# schematic_solved.net
KiCad netlist of a schematic drawn in EAGLE
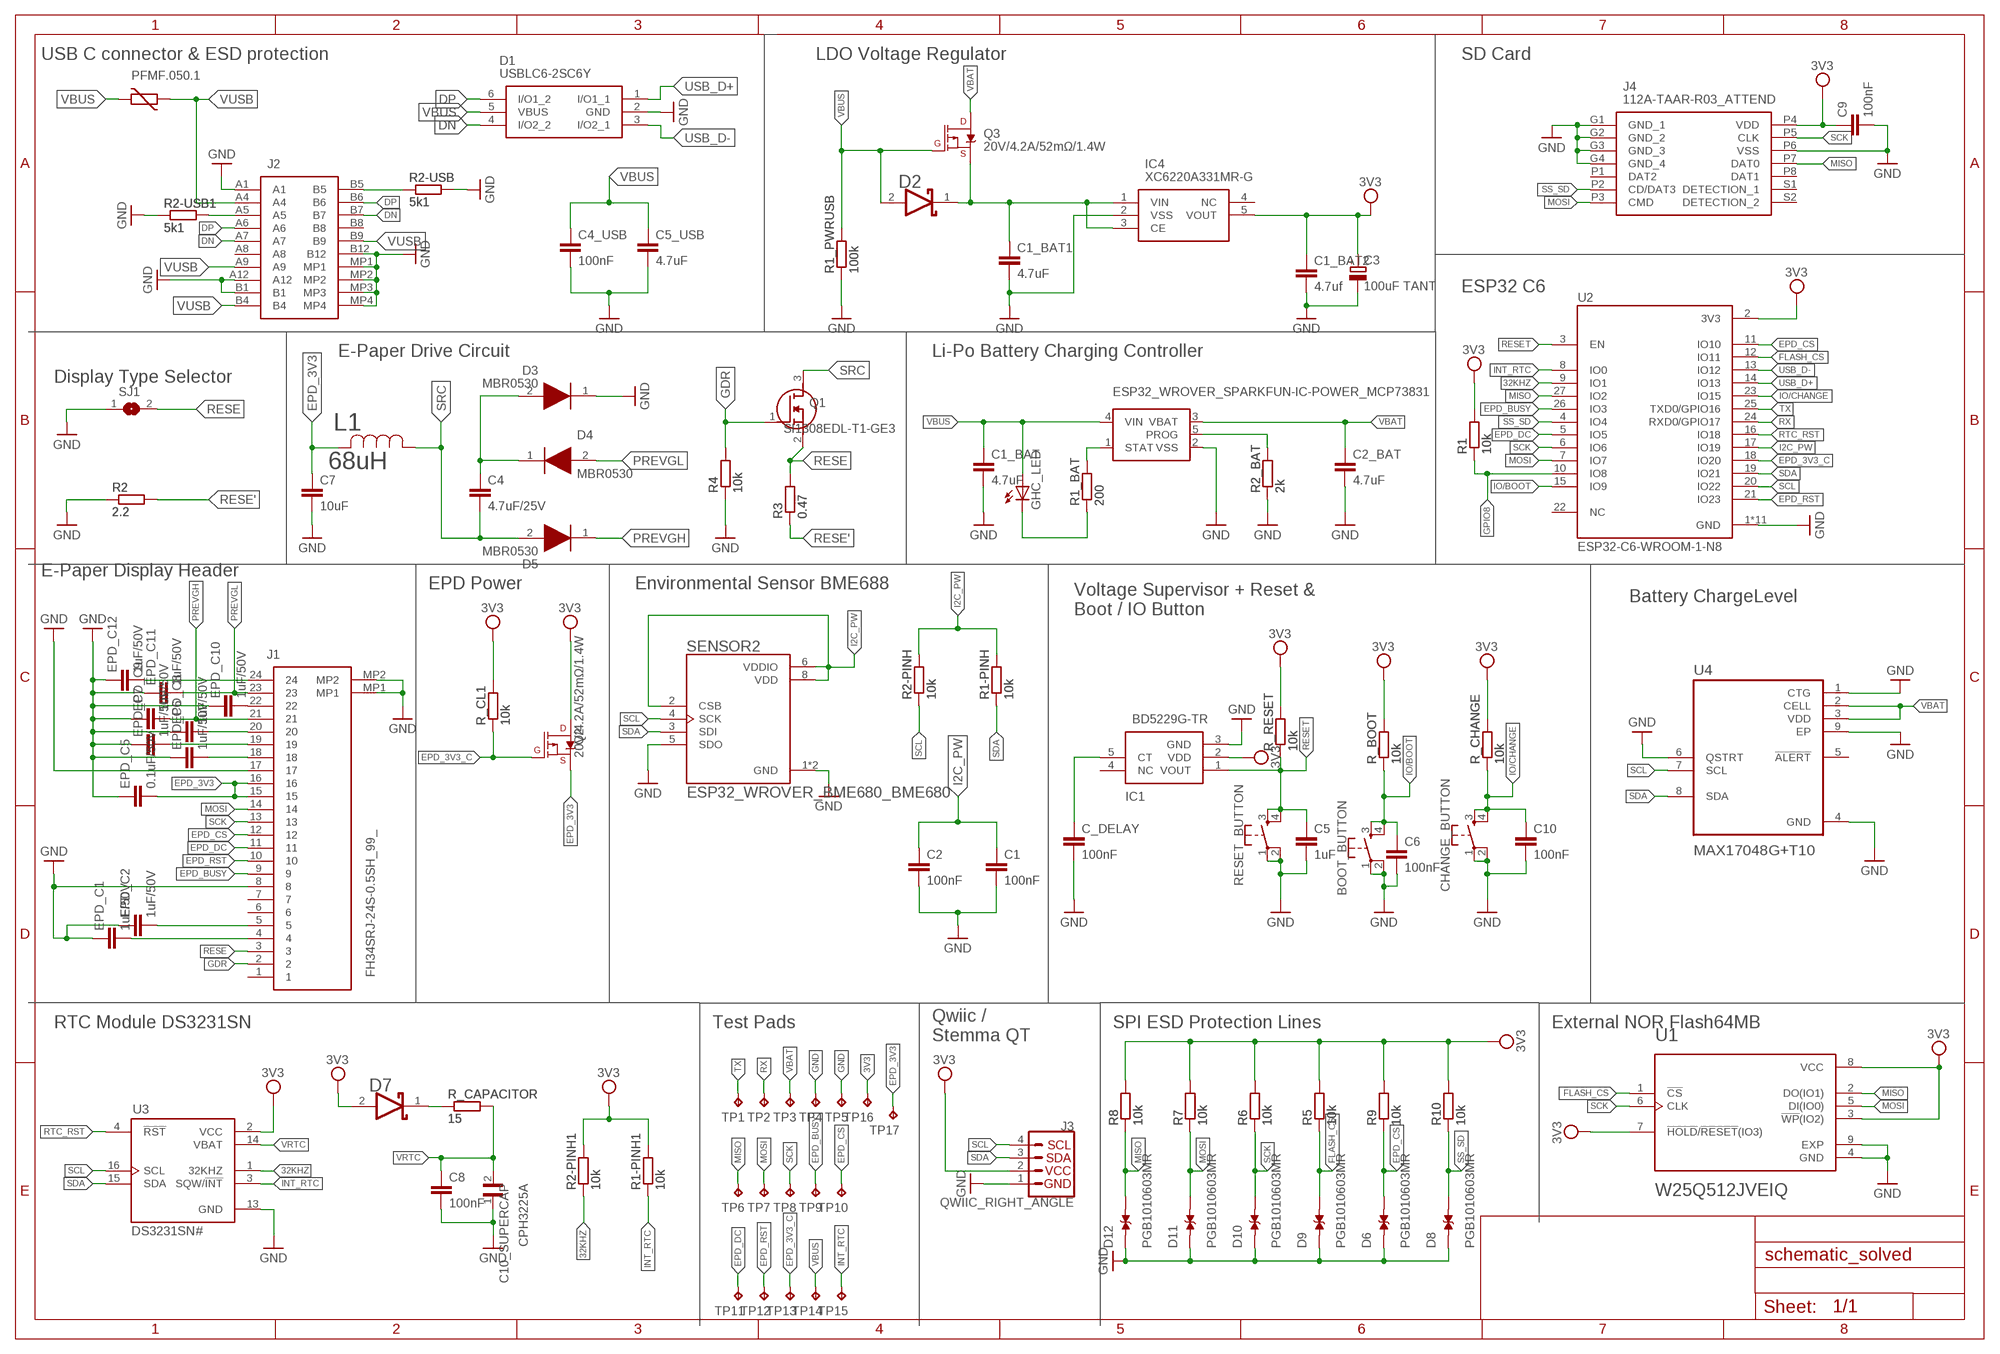
[diagram p0: schematic, sheet 1]

(export (version "E")
  (design (tool "Eeschema 10.0.6"))
  (components
    (comp (ref "BOOT_BUTTON")
      (value "BUTTON_CUSYOMV1")
      (footprint "eagle-import:MYBUTTON")
      (libsource (lib "eagle-import") (part "BUTTON_CUSYOMV1"))
    )
    (comp (ref "C1")
      (value "100nF")
      (footprint "eagle-import:ESP32_WROVER_EAGLE-LTSPICE_C0402")
      (libsource (lib "eagle-import") (part "ESP32_WROVER_EAGLE-LTSPICE_CC0402"))
    )
    (comp (ref "C1_BAT")
      (value "4.7uF")
      (footprint "eagle-import:EAGLE-LTSPICE_C0402")
      (libsource (lib "eagle-import") (part "EAGLE-LTSPICE_CC0402"))
    )
    (comp (ref "C1_BAT1")
      (value "4.7uF")
      (footprint "eagle-import:EAGLE-LTSPICE_C0402")
      (libsource (lib "eagle-import") (part "EAGLE-LTSPICE_CC0402"))
    )
    (comp (ref "C1_BAT2")
      (value "4.7uf")
      (footprint "eagle-import:EAGLE-LTSPICE_C0402")
      (libsource (lib "eagle-import") (part "EAGLE-LTSPICE_CC0402"))
    )
    (comp (ref "C2")
      (value "100nF")
      (footprint "eagle-import:ESP32_WROVER_EAGLE-LTSPICE_C0402")
      (libsource (lib "eagle-import") (part "ESP32_WROVER_EAGLE-LTSPICE_CC0402"))
    )
    (comp (ref "C2_BAT")
      (value "4.7uF")
      (footprint "eagle-import:EAGLE-LTSPICE_C0402")
      (libsource (lib "eagle-import") (part "EAGLE-LTSPICE_CC0402"))
    )
    (comp (ref "C3")
      (value "100uF TANT")
      (footprint "eagle-import:RCL_CT3528")
      (libsource (lib "eagle-import") (part "RCL_CPOL-EUCT3528"))
    )
    (comp (ref "C4")
      (value "4.7uF/25V")
      (footprint "eagle-import:ESP32_WROVER_EAGLE-LTSPICE_C0402")
      (libsource (lib "eagle-import") (part "ESP32_WROVER_EAGLE-LTSPICE_CC0402"))
    )
    (comp (ref "C4_USB")
      (value "100nF")
      (footprint "eagle-import:ESP32_WROVER_EAGLE-LTSPICE_C0402")
      (libsource (lib "eagle-import") (part "ESP32_WROVER_EAGLE-LTSPICE_CC0402"))
    )
    (comp (ref "C5")
      (value "1uF")
      (footprint "eagle-import:ESP32_WROVER_EAGLE-LTSPICE_C0402")
      (libsource (lib "eagle-import") (part "ESP32_WROVER_EAGLE-LTSPICE_CC0402"))
    )
    (comp (ref "C5_USB")
      (value "4.7uF")
      (footprint "eagle-import:ESP32_WROVER_EAGLE-LTSPICE_C0402")
      (libsource (lib "eagle-import") (part "ESP32_WROVER_EAGLE-LTSPICE_CC0402"))
    )
    (comp (ref "C6")
      (value "100nF")
      (footprint "eagle-import:ESP32_WROVER_EAGLE-LTSPICE_C0402")
      (libsource (lib "eagle-import") (part "ESP32_WROVER_EAGLE-LTSPICE_CC0402"))
    )
    (comp (ref "C7")
      (value "10uF")
      (footprint "eagle-import:ESP32_WROVER_EAGLE-LTSPICE_C0402")
      (libsource (lib "eagle-import") (part "ESP32_WROVER_EAGLE-LTSPICE_CC0402"))
    )
    (comp (ref "C8")
      (value "100nF")
      (footprint "eagle-import:ESP32_WROVER_EAGLE-LTSPICE_C0402")
      (libsource (lib "eagle-import") (part "ESP32_WROVER_EAGLE-LTSPICE_CC0402"))
    )
    (comp (ref "C9")
      (value "100nF")
      (footprint "eagle-import:ESP32_WROVER_EAGLE-LTSPICE_C0402")
      (libsource (lib "eagle-import") (part "ESP32_WROVER_EAGLE-LTSPICE_CC0402"))
    )
    (comp (ref "C10")
      (value "100nF")
      (footprint "eagle-import:ESP32_WROVER_EAGLE-LTSPICE_C0402")
      (libsource (lib "eagle-import") (part "ESP32_WROVER_EAGLE-LTSPICE_CC0402"))
    )
    (comp (ref "C10_SUPERCAP")
      (value "CPH3225A")
      (footprint "eagle-import:CAPCP3225X100N")
      (fields (field (name "MF") "Seiko Instruments"))
      (libsource (lib "eagle-import") (part "CPH3225A"))
    )
    (comp (ref "CHANGE_BUTTON")
      (value "BUTTON_CUSYOMV1")
      (footprint "eagle-import:MYBUTTON")
      (libsource (lib "eagle-import") (part "BUTTON_CUSYOMV1"))
    )
    (comp (ref "C_DELAY")
      (value "100nF")
      (footprint "eagle-import:ESP32_WROVER_EAGLE-LTSPICE_C0402")
      (libsource (lib "eagle-import") (part "ESP32_WROVER_EAGLE-LTSPICE_CC0402"))
    )
    (comp (ref "D1")
      (value "USBLC6-2SC6Y")
      (footprint "eagle-import:SOT95P280X145-6N")
      (fields (field (name "MF") "STMicroelectronics"))
      (libsource (lib "eagle-import") (part "USBLC6-2SC6Y"))
    )
    (comp (ref "D2")
      (value "ESP32_WROVER_AVX---SD0805S020S1R0_AVX_SD0805S020S1R0_0_0AVX_SD0805S020S1R0_0_0")
      (footprint "eagle-import:ESP32_WROVER_AVX---SD0805S020S1R0_AVX_SD0805S020S1R0_0")
      (fields
        (field (name "DIGIKEY_PART_NUMBER") "478-7800-1-ND")
        (field (name "MF") "AVX")
        (field (name "MOUSER_PART_NUMBER") "581-SD0805S020S1R0")
      )
      (libsource (lib "eagle-import") (part "ESP32_WROVER_AVX---SD0805S020S1R0_AVX_SD0805S020S1R0_0_0AVX_SD0805S020S1R0_0_0"))
    )
    (comp (ref "D3")
      (value "MBR0530")
      (footprint "eagle-import:SOD3716X135N")
      (fields (field (name "MF") "ON Semiconductor"))
      (libsource (lib "eagle-import") (part "MBR0530"))
    )
    (comp (ref "D4")
      (value "MBR0530")
      (footprint "eagle-import:SOD3716X135N")
      (fields (field (name "MF") "ON Semiconductor"))
      (libsource (lib "eagle-import") (part "MBR0530"))
    )
    (comp (ref "D5")
      (value "MBR0530")
      (footprint "eagle-import:SOD3716X135N")
      (fields (field (name "MF") "ON Semiconductor"))
      (libsource (lib "eagle-import") (part "MBR0530"))
    )
    (comp (ref "D6")
      (value "PGB1010603MR")
      (footprint "eagle-import:DIOC1608X36N")
      (fields (field (name "MF") "Littelfuse Inc."))
      (libsource (lib "eagle-import") (part "PGB1010603MR"))
    )
    (comp (ref "D7")
      (value "ESP32_WROVER_AVX---SD0805S020S1R0_AVX_SD0805S020S1R0_0_0AVX_SD0805S020S1R0_0_0")
      (footprint "eagle-import:ESP32_WROVER_AVX---SD0805S020S1R0_AVX_SD0805S020S1R0_0")
      (fields
        (field (name "DIGIKEY_PART_NUMBER") "478-7800-1-ND")
        (field (name "MF") "AVX")
        (field (name "MOUSER_PART_NUMBER") "581-SD0805S020S1R0")
      )
      (libsource (lib "eagle-import") (part "ESP32_WROVER_AVX---SD0805S020S1R0_AVX_SD0805S020S1R0_0_0AVX_SD0805S020S1R0_0_0"))
    )
    (comp (ref "D8")
      (value "PGB1010603MR")
      (footprint "eagle-import:DIOC1608X36N")
      (fields (field (name "MF") "Littelfuse Inc."))
      (libsource (lib "eagle-import") (part "PGB1010603MR"))
    )
    (comp (ref "D9")
      (value "PGB1010603MR")
      (footprint "eagle-import:DIOC1608X36N")
      (fields (field (name "MF") "Littelfuse Inc."))
      (libsource (lib "eagle-import") (part "PGB1010603MR"))
    )
    (comp (ref "D10")
      (value "PGB1010603MR")
      (footprint "eagle-import:DIOC1608X36N")
      (fields (field (name "MF") "Littelfuse Inc."))
      (libsource (lib "eagle-import") (part "PGB1010603MR"))
    )
    (comp (ref "D11")
      (value "PGB1010603MR")
      (footprint "eagle-import:DIOC1608X36N")
      (fields (field (name "MF") "Littelfuse Inc."))
      (libsource (lib "eagle-import") (part "PGB1010603MR"))
    )
    (comp (ref "D12")
      (value "PGB1010603MR")
      (footprint "eagle-import:DIOC1608X36N")
      (fields (field (name "MF") "Littelfuse Inc."))
      (libsource (lib "eagle-import") (part "PGB1010603MR"))
    )
    (comp (ref "EPD_C1")
      (value "1uF/50V")
      (footprint "eagle-import:ESP32_WROVER_EAGLE-LTSPICE_C0402")
      (libsource (lib "eagle-import") (part "ESP32_WROVER_EAGLE-LTSPICE_CC0402"))
    )
    (comp (ref "EPD_C2")
      (value "1uF/50V")
      (footprint "eagle-import:ESP32_WROVER_EAGLE-LTSPICE_C0402")
      (libsource (lib "eagle-import") (part "ESP32_WROVER_EAGLE-LTSPICE_CC0402"))
    )
    (comp (ref "EPD_C5")
      (value "0.1uF/50V")
      (footprint "eagle-import:ESP32_WROVER_EAGLE-LTSPICE_C0402")
      (libsource (lib "eagle-import") (part "ESP32_WROVER_EAGLE-LTSPICE_CC0402"))
    )
    (comp (ref "EPD_C6")
      (value "1uF/50V")
      (footprint "eagle-import:ESP32_WROVER_EAGLE-LTSPICE_C0402")
      (libsource (lib "eagle-import") (part "ESP32_WROVER_EAGLE-LTSPICE_CC0402"))
    )
    (comp (ref "EPD_C7")
      (value "1uF/50V")
      (footprint "eagle-import:ESP32_WROVER_EAGLE-LTSPICE_C0402")
      (libsource (lib "eagle-import") (part "ESP32_WROVER_EAGLE-LTSPICE_CC0402"))
    )
    (comp (ref "EPD_C8")
      (value "1uF/50V")
      (footprint "eagle-import:ESP32_WROVER_EAGLE-LTSPICE_C0402")
      (libsource (lib "eagle-import") (part "ESP32_WROVER_EAGLE-LTSPICE_CC0402"))
    )
    (comp (ref "EPD_C9")
      (value "1uF/50V")
      (footprint "eagle-import:ESP32_WROVER_EAGLE-LTSPICE_C0402")
      (libsource (lib "eagle-import") (part "ESP32_WROVER_EAGLE-LTSPICE_CC0402"))
    )
    (comp (ref "EPD_C10")
      (value "1uF/50V")
      (footprint "eagle-import:ESP32_WROVER_EAGLE-LTSPICE_C0402")
      (libsource (lib "eagle-import") (part "ESP32_WROVER_EAGLE-LTSPICE_CC0402"))
    )
    (comp (ref "EPD_C11")
      (value "1uF/50V")
      (footprint "eagle-import:ESP32_WROVER_EAGLE-LTSPICE_C0402")
      (libsource (lib "eagle-import") (part "ESP32_WROVER_EAGLE-LTSPICE_CC0402"))
    )
    (comp (ref "EPD_C12")
      (value "1uF/50V")
      (footprint "eagle-import:ESP32_WROVER_EAGLE-LTSPICE_C0402")
      (libsource (lib "eagle-import") (part "ESP32_WROVER_EAGLE-LTSPICE_CC0402"))
    )
    (comp (ref "GHC_LED")
      (value "ADAFRUIT_LEDCHIP-LED0603")
      (footprint "eagle-import:ADAFRUIT_CHIP-LED0603")
      (libsource (lib "eagle-import") (part "ADAFRUIT_LEDCHIP-LED0603"))
    )
    (comp (ref "IC1")
      (value "BD5229G-TR")
      (footprint "eagle-import:SOT95P280X125-5N")
      (fields (field (name "MOUSER_PART_NUMBER") "755-BD5229G-TR"))
      (libsource (lib "eagle-import") (part "BD5229G-TR"))
    )
    (comp (ref "IC4")
      (value "XC6220A331MR-G")
      (footprint "eagle-import:SOT95P280X120-5N")
      (fields (field (name "MOUSER_PART_NUMBER") "865-XC6220A331MR-G"))
      (libsource (lib "eagle-import") (part "XC6220A331MR-G"))
    )
    (comp (ref "J1")
      (value "FH34SRJ-24S-0.5SH_99_")
      (footprint "eagle-import:FH34SRJ24S05SH99")
      (fields
        (field (name "MANUFACTURER_PART_NUMBER") "FH34SRJ-24S-0.5SH(99)")
        (field (name "MOUSER_PART_NUMBER") "798-FH34SRJ24S05SH99")
      )
      (libsource (lib "eagle-import") (part "FH34SRJ-24S-0.5SH_99_"))
    )
    (comp (ref "J2")
      (value "SAMACSYS_PARTS_USB4110-GF-A")
      (footprint "eagle-import:SAMACSYS_PARTS_USB4110GFA")
      (fields
        (field (name "MANUFACTURER_PART_NUMBER") "USB4110-GF-A")
        (field (name "MOUSER_PART_NUMBER") "640-USB4110-GF-A")
      )
      (libsource (lib "eagle-import") (part "SAMACSYS_PARTS_USB4110-GF-A"))
    )
    (comp (ref "J3")
      (value "QWIIC_RIGHT_ANGLE")
      (footprint "eagle-import:JST04_1MM_RA")
      (libsource (lib "eagle-import") (part "QWIIC_CONNECTORJS-1MM"))
    )
    (comp (ref "J4")
      (value "112A-TAAR-R03_ATTEND")
      (footprint "eagle-import:112ATAARR03ATTEND")
      (fields (field (name "MANUFACTURER_PART_NUMBER") "112A-TAAR-R03 ATTEND"))
      (libsource (lib "eagle-import") (part "112A-TAAR-R03_ATTEND"))
    )
    (comp (ref "L1")
      (value "68uH")
      (footprint "eagle-import:IND_4828-WE-TPC_WRE")
      (fields
        (field (name "MANUFACTURER_PART_NUMBER") "744043680")
        (field (name "COPYRIGHT") "Copyright (C) 2024 Ultra Librarian. All rights reserved.")
      )
      (libsource (lib "eagle-import") (part "744043680IND_4828-WE-TPC_WRE"))
    )
    (comp (ref "PFMF.050.1")
      (value "ESP32C6_VARISTORCN1812")
      (footprint "eagle-import:ESP32C6_VARISTOR_CT_CN1812")
      (libsource (lib "eagle-import") (part "ESP32C6_VARISTORCN1812"))
    )
    (comp (ref "Q1")
      (value "SI1308EDL-T1-GE3")
      (footprint "eagle-import:SOT65P210X110-3N")
      (fields (field (name "MF") "Vishay Siliconix"))
      (libsource (lib "eagle-import") (part "SI1308EDL-T1-GE3"))
    )
    (comp (ref "Q2")
      (value "20V/4.2A/52mΩ/1.4W")
      (footprint "eagle-import:ESP32_WROVER_SPARKFUN-DISCRETESEMI_SOT23-3")
      (libsource (lib "eagle-import") (part "ESP32_WROVER_SPARKFUN-DISCRETESEMI_MOSFET_PCH-DMG2305UX-7"))
    )
    (comp (ref "Q3")
      (value "20V/4.2A/52mΩ/1.4W")
      (footprint "eagle-import:ESP32_WROVER_SPARKFUN-DISCRETESEMI_SOT23-3")
      (libsource (lib "eagle-import") (part "ESP32_WROVER_SPARKFUN-DISCRETESEMI_MOSFET_PCH-DMG2305UX-7"))
    )
    (comp (ref "R1")
      (value "10k")
      (footprint "eagle-import:ESP32_WROVER_EAGLE-LTSPICE_R0402")
      (libsource (lib "eagle-import") (part "ESP32_WROVER_EAGLE-LTSPICE_RR0402"))
    )
    (comp (ref "R1-PINH")
      (value "10k")
      (footprint "eagle-import:ESP32_WROVER_EAGLE-LTSPICE_R0402")
      (libsource (lib "eagle-import") (part "ESP32_WROVER_EAGLE-LTSPICE_RR0402"))
    )
    (comp (ref "R1-PINH1")
      (value "10k")
      (footprint "eagle-import:ESP32_WROVER_EAGLE-LTSPICE_R0402")
      (libsource (lib "eagle-import") (part "ESP32_WROVER_EAGLE-LTSPICE_RR0402"))
    )
    (comp (ref "R1_BAT")
      (value "200")
      (footprint "eagle-import:ESP32_WROVER_EAGLE-LTSPICE_R0402")
      (libsource (lib "eagle-import") (part "ESP32_WROVER_EAGLE-LTSPICE_RR0402"))
    )
    (comp (ref "R1_PWRUSB")
      (value "100k")
      (footprint "eagle-import:ESP32_WROVER_EAGLE-LTSPICE_R0402")
      (libsource (lib "eagle-import") (part "ESP32_WROVER_EAGLE-LTSPICE_RR0402"))
    )
    (comp (ref "R2")
      (value "2.2")
      (footprint "eagle-import:ESP32_WROVER_EAGLE-LTSPICE_R0402")
      (libsource (lib "eagle-import") (part "ESP32_WROVER_EAGLE-LTSPICE_RR0402"))
    )
    (comp (ref "R2-PINH")
      (value "10k")
      (footprint "eagle-import:ESP32_WROVER_EAGLE-LTSPICE_R0402")
      (libsource (lib "eagle-import") (part "ESP32_WROVER_EAGLE-LTSPICE_RR0402"))
    )
    (comp (ref "R2-PINH1")
      (value "10k")
      (footprint "eagle-import:ESP32_WROVER_EAGLE-LTSPICE_R0402")
      (libsource (lib "eagle-import") (part "ESP32_WROVER_EAGLE-LTSPICE_RR0402"))
    )
    (comp (ref "R2-USB")
      (value "5k1")
      (footprint "eagle-import:ESP32_WROVER_EAGLE-LTSPICE_R0402")
      (libsource (lib "eagle-import") (part "ESP32_WROVER_EAGLE-LTSPICE_RR0402"))
    )
    (comp (ref "R2-USB1")
      (value "5k1")
      (footprint "eagle-import:ESP32_WROVER_EAGLE-LTSPICE_R0402")
      (libsource (lib "eagle-import") (part "ESP32_WROVER_EAGLE-LTSPICE_RR0402"))
    )
    (comp (ref "R2_BAT")
      (value "2k")
      (footprint "eagle-import:ESP32_WROVER_EAGLE-LTSPICE_R0402")
      (libsource (lib "eagle-import") (part "ESP32_WROVER_EAGLE-LTSPICE_RR0402"))
    )
    (comp (ref "R3")
      (value "0.47")
      (footprint "eagle-import:ESP32_WROVER_EAGLE-LTSPICE_R0402")
      (libsource (lib "eagle-import") (part "ESP32_WROVER_EAGLE-LTSPICE_RR0402"))
    )
    (comp (ref "R4")
      (value "10k")
      (footprint "eagle-import:ESP32_WROVER_EAGLE-LTSPICE_R0402")
      (libsource (lib "eagle-import") (part "ESP32_WROVER_EAGLE-LTSPICE_RR0402"))
    )
    (comp (ref "R5")
      (value "10k")
      (footprint "eagle-import:ESP32_WROVER_EAGLE-LTSPICE_R0402")
      (libsource (lib "eagle-import") (part "ESP32_WROVER_EAGLE-LTSPICE_RR0402"))
    )
    (comp (ref "R6")
      (value "10k")
      (footprint "eagle-import:ESP32_WROVER_EAGLE-LTSPICE_R0402")
      (libsource (lib "eagle-import") (part "ESP32_WROVER_EAGLE-LTSPICE_RR0402"))
    )
    (comp (ref "R7")
      (value "10k")
      (footprint "eagle-import:ESP32_WROVER_EAGLE-LTSPICE_R0402")
      (libsource (lib "eagle-import") (part "ESP32_WROVER_EAGLE-LTSPICE_RR0402"))
    )
    (comp (ref "R8")
      (value "10k")
      (footprint "eagle-import:ESP32_WROVER_EAGLE-LTSPICE_R0402")
      (libsource (lib "eagle-import") (part "ESP32_WROVER_EAGLE-LTSPICE_RR0402"))
    )
    (comp (ref "R9")
      (value "10k")
      (footprint "eagle-import:ESP32_WROVER_EAGLE-LTSPICE_R0402")
      (libsource (lib "eagle-import") (part "ESP32_WROVER_EAGLE-LTSPICE_RR0402"))
    )
    (comp (ref "R10")
      (value "10k")
      (footprint "eagle-import:ESP32_WROVER_EAGLE-LTSPICE_R0402")
      (libsource (lib "eagle-import") (part "ESP32_WROVER_EAGLE-LTSPICE_RR0402"))
    )
    (comp (ref "RESET_BUTTON")
      (value "BUTTON_CUSYOMV1")
      (footprint "eagle-import:MYBUTTON")
      (libsource (lib "eagle-import") (part "BUTTON_CUSYOMV1"))
    )
    (comp (ref "R_BOOT")
      (value "10k")
      (footprint "eagle-import:ESP32_WROVER_EAGLE-LTSPICE_R0402")
      (libsource (lib "eagle-import") (part "ESP32_WROVER_EAGLE-LTSPICE_RR0402"))
    )
    (comp (ref "R_CAPACITOR")
      (value "15")
      (footprint "eagle-import:ESP32_WROVER_EAGLE-LTSPICE_R0402")
      (libsource (lib "eagle-import") (part "ESP32_WROVER_EAGLE-LTSPICE_RR0402"))
    )
    (comp (ref "R_CHANGE")
      (value "10k")
      (footprint "eagle-import:ESP32_WROVER_EAGLE-LTSPICE_R0402")
      (libsource (lib "eagle-import") (part "ESP32_WROVER_EAGLE-LTSPICE_RR0402"))
    )
    (comp (ref "R_CL1")
      (value "10k")
      (footprint "eagle-import:ESP32_WROVER_EAGLE-LTSPICE_R0402")
      (libsource (lib "eagle-import") (part "ESP32_WROVER_EAGLE-LTSPICE_RR0402"))
    )
    (comp (ref "R_RESET")
      (value "10k")
      (footprint "eagle-import:ESP32_WROVER_EAGLE-LTSPICE_R0402")
      (libsource (lib "eagle-import") (part "ESP32_WROVER_EAGLE-LTSPICE_RR0402"))
    )
    (comp (ref "SENSOR2")
      (value "ESP32_WROVER_BME680_BME680")
      (footprint "eagle-import:ESP32_WROVER_BME680_PSON80P300X300X100-8N")
      (fields (field (name "MF") "Bosch Sensortec") (field (name "MP") "BME680"))
      (libsource (lib "eagle-import") (part "ESP32_WROVER_BME680_BME680"))
    )
    (comp (ref "SJ1") (value "SJ") (footprint "eagle-import:SJ") (libsource (lib "eagle-import") (part "SJ")))
    (comp (ref "TP1")
      (value "TPTP20R")
      (footprint "eagle-import:TP20R")
      (libsource (lib "eagle-import") (part "TPTP20R"))
    )
    (comp (ref "TP2")
      (value "TPTP20R")
      (footprint "eagle-import:TP20R")
      (libsource (lib "eagle-import") (part "TPTP20R"))
    )
    (comp (ref "TP3")
      (value "TPTP20R")
      (footprint "eagle-import:TP20R")
      (libsource (lib "eagle-import") (part "TPTP20R"))
    )
    (comp (ref "TP4")
      (value "TPTP20R")
      (footprint "eagle-import:TP20R")
      (libsource (lib "eagle-import") (part "TPTP20R"))
    )
    (comp (ref "TP5")
      (value "TPTP20R")
      (footprint "eagle-import:TP20R")
      (libsource (lib "eagle-import") (part "TPTP20R"))
    )
    (comp (ref "TP6")
      (value "TPTP20R")
      (footprint "eagle-import:TP20R")
      (libsource (lib "eagle-import") (part "TPTP20R"))
    )
    (comp (ref "TP7")
      (value "TPTP20R")
      (footprint "eagle-import:TP20R")
      (libsource (lib "eagle-import") (part "TPTP20R"))
    )
    (comp (ref "TP8")
      (value "TPTP20R")
      (footprint "eagle-import:TP20R")
      (libsource (lib "eagle-import") (part "TPTP20R"))
    )
    (comp (ref "TP9")
      (value "TPTP20R")
      (footprint "eagle-import:TP20R")
      (libsource (lib "eagle-import") (part "TPTP20R"))
    )
    (comp (ref "TP10")
      (value "TPTP20R")
      (footprint "eagle-import:TP20R")
      (libsource (lib "eagle-import") (part "TPTP20R"))
    )
    (comp (ref "TP11")
      (value "TPTP20R")
      (footprint "eagle-import:TP20R")
      (libsource (lib "eagle-import") (part "TPTP20R"))
    )
    (comp (ref "TP12")
      (value "TPTP20R")
      (footprint "eagle-import:TP20R")
      (libsource (lib "eagle-import") (part "TPTP20R"))
    )
    (comp (ref "TP13")
      (value "TPTP20R")
      (footprint "eagle-import:TP20R")
      (libsource (lib "eagle-import") (part "TPTP20R"))
    )
    (comp (ref "TP14")
      (value "TPTP20R")
      (footprint "eagle-import:TP20R")
      (libsource (lib "eagle-import") (part "TPTP20R"))
    )
    (comp (ref "TP15")
      (value "TPTP20R")
      (footprint "eagle-import:TP20R")
      (libsource (lib "eagle-import") (part "TPTP20R"))
    )
    (comp (ref "TP16")
      (value "TPTP20R")
      (footprint "eagle-import:TP20R")
      (libsource (lib "eagle-import") (part "TPTP20R"))
    )
    (comp (ref "TP17")
      (value "TPTP20R")
      (footprint "eagle-import:TP20R")
      (libsource (lib "eagle-import") (part "TPTP20R"))
    )
    (comp (ref "U")
      (value "ESP32_WROVER_SPARKFUN-IC-POWER_MCP73831")
      (footprint "eagle-import:ESP32_WROVER_SPARKFUN-IC-POWER_SOT23-5")
      (libsource (lib "eagle-import") (part "ESP32_WROVER_SPARKFUN-IC-POWER_MCP73831"))
    )
    (comp (ref "U1")
      (value "W25Q512JVEIQ")
      (footprint "eagle-import:SON127P600X800X80-9N")
      (fields (field (name "MF") "Winbond Electronics"))
      (libsource (lib "eagle-import") (part "W25Q512JVEIQ"))
    )
    (comp (ref "U2")
      (value "ESP32-C6-WROOM-1-N8")
      (footprint "eagle-import:XCVR_ESP32-C6-WROOM-1-N8")
      (fields (field (name "MF") "Espressif Systems"))
      (libsource (lib "eagle-import") (part "ESP32-C6-WROOM-1-N8"))
    )
    (comp (ref "U3")
      (value "DS3231SN#")
      (footprint "eagle-import:SOIC127P1032X265-16N")
      (fields (field (name "MF") "Analog Devices"))
      (libsource (lib "eagle-import") (part "DS3231SN#"))
    )
    (comp (ref "U4")
      (value "MAX17048G+T10")
      (footprint "eagle-import:SON50P200X200X80-9N")
      (fields (field (name "MF") "Analog Devices"))
      (libsource (lib "eagle-import") (part "MAX17048G+T10"))
    )
  )
  (nets
    (net (code "1") (name "3V3") (class "Default")
      (node (ref "C1_BAT2") (pin "1") (pinfunction "1_1") (pintype "passive"))
      (node (ref "C3") (pin "+") (pinfunction "+_+") (pintype "passive"))
      (node (ref "C9") (pin "1") (pinfunction "1_1") (pintype "passive"))
      (node (ref "D7") (pin "2") (pinfunction "ANODE_2") (pintype "bidirectional"))
      (node (ref "IC1") (pin "2") (pinfunction "VDD_2") (pintype "bidirectional"))
      (node (ref "IC4") (pin "5") (pinfunction "VOUT_5") (pintype "bidirectional"))
      (node (ref "J3") (pin "2") (pinfunction "2_2") (pintype "power_in"))
      (node (ref "J4") (pin "P4") (pinfunction "VDD_P4") (pintype "bidirectional"))
      (node (ref "Q2") (pin "3") (pinfunction "D_3") (pintype "bidirectional"))
      (node (ref "R1") (pin "2") (pinfunction "2_2") (pintype "passive"))
      (node (ref "R1-PINH1") (pin "2") (pinfunction "2_2") (pintype "passive"))
      (node (ref "R10") (pin "2") (pinfunction "2_2") (pintype "passive"))
      (node (ref "R2-PINH1") (pin "2") (pinfunction "2_2") (pintype "passive"))
      (node (ref "R5") (pin "2") (pinfunction "2_2") (pintype "passive"))
      (node (ref "R6") (pin "2") (pinfunction "2_2") (pintype "passive"))
      (node (ref "R7") (pin "2") (pinfunction "2_2") (pintype "passive"))
      (node (ref "R8") (pin "2") (pinfunction "2_2") (pintype "passive"))
      (node (ref "R9") (pin "2") (pinfunction "2_2") (pintype "passive"))
      (node (ref "R_BOOT") (pin "2") (pinfunction "2_2") (pintype "passive"))
      (node (ref "R_CHANGE") (pin "2") (pinfunction "2_2") (pintype "passive"))
      (node (ref "R_CL1") (pin "2") (pinfunction "2_2") (pintype "passive"))
      (node (ref "R_RESET") (pin "2") (pinfunction "2_2") (pintype "passive"))
      (node (ref "TP16") (pin "TP") (pinfunction "TP_TP") (pintype "input"))
      (node (ref "U1") (pin "3") (pinfunction "~{WP}(IO2)_3") (pintype "bidirectional"))
      (node (ref "U1") (pin "7") (pinfunction "~{HOLD}/~{RESET}(IO3)_7") (pintype "bidirectional"))
      (node (ref "U1") (pin "8") (pinfunction "VCC_8") (pintype "power_in"))
      (node (ref "U2") (pin "2") (pinfunction "3V3_2") (pintype "power_in"))
      (node (ref "U3") (pin "2") (pinfunction "VCC_2") (pintype "power_in"))
    )
    (net (code "2") (name "32KHZ") (class "Default")
      (node (ref "R2-PINH1") (pin "1") (pinfunction "1_1") (pintype "passive"))
      (node (ref "U2") (pin "9") (pinfunction "IO1_9") (pintype "bidirectional"))
      (node (ref "U3") (pin "1") (pinfunction "32KHZ_1") (pintype "output"))
    )
    (net (code "3") (name "DN") (class "Default")
      (node (ref "D1") (pin "4") (pinfunction "I/O2_2_4") (pintype "bidirectional"))
      (node (ref "J2") (pin "A7") (pinfunction "A7_A7") (pintype "bidirectional"))
      (node (ref "J2") (pin "B7") (pinfunction "B7_B7") (pintype "bidirectional"))
    )
    (net (code "4") (name "DP") (class "Default")
      (node (ref "D1") (pin "6") (pinfunction "I/O1_2_6") (pintype "bidirectional"))
      (node (ref "J2") (pin "A6") (pinfunction "A6_A6") (pintype "bidirectional"))
      (node (ref "J2") (pin "B6") (pinfunction "B6_B6") (pintype "bidirectional"))
    )
    (net (code "5") (name "EPD_3V3") (class "Default")
      (node (ref "C7") (pin "1") (pinfunction "1_1") (pintype "passive"))
      (node (ref "EPD_C5") (pin "2") (pinfunction "2_2") (pintype "passive"))
      (node (ref "J1") (pin "15") (pinfunction "15_15") (pintype "bidirectional"))
      (node (ref "J1") (pin "16") (pinfunction "16_16") (pintype "bidirectional"))
      (node (ref "L1") (pin "2") (pinfunction "2_2") (pintype "passive"))
      (node (ref "Q2") (pin "2") (pinfunction "S_2") (pintype "bidirectional"))
      (node (ref "TP17") (pin "TP") (pinfunction "TP_TP") (pintype "input"))
    )
    (net (code "6") (name "EPD_3V3_C") (class "Default")
      (node (ref "Q2") (pin "1") (pinfunction "G_1") (pintype "bidirectional"))
      (node (ref "R_CL1") (pin "1") (pinfunction "1_1") (pintype "passive"))
      (node (ref "TP13") (pin "TP") (pinfunction "TP_TP") (pintype "input"))
      (node (ref "U2") (pin "18") (pinfunction "IO20_18") (pintype "bidirectional"))
    )
    (net (code "7") (name "EPD_BUSY") (class "Default")
      (node (ref "J1") (pin "9") (pinfunction "9_9") (pintype "bidirectional"))
      (node (ref "TP9") (pin "TP") (pinfunction "TP_TP") (pintype "input"))
      (node (ref "U2") (pin "26") (pinfunction "IO3_26") (pintype "bidirectional"))
    )
    (net (code "8") (name "EPD_CS") (class "Default")
      (node (ref "D6") (pin "2") (pinfunction "2_2") (pintype "passive"))
      (node (ref "J1") (pin "12") (pinfunction "12_12") (pintype "bidirectional"))
      (node (ref "R9") (pin "1") (pinfunction "1_1") (pintype "passive"))
      (node (ref "TP10") (pin "TP") (pinfunction "TP_TP") (pintype "input"))
      (node (ref "U2") (pin "11") (pinfunction "IO10_11") (pintype "bidirectional"))
    )
    (net (code "9") (name "EPD_DC") (class "Default")
      (node (ref "J1") (pin "11") (pinfunction "11_11") (pintype "bidirectional"))
      (node (ref "TP11") (pin "TP") (pinfunction "TP_TP") (pintype "input"))
      (node (ref "U2") (pin "5") (pinfunction "IO5_5") (pintype "bidirectional"))
    )
    (net (code "10") (name "EPD_RST") (class "Default")
      (node (ref "J1") (pin "10") (pinfunction "10_10") (pintype "bidirectional"))
      (node (ref "TP12") (pin "TP") (pinfunction "TP_TP") (pintype "input"))
      (node (ref "U2") (pin "21") (pinfunction "IO23_21") (pintype "bidirectional"))
    )
    (net (code "11") (name "FLASH_CS") (class "Default")
      (node (ref "D9") (pin "2") (pinfunction "2_2") (pintype "passive"))
      (node (ref "R5") (pin "1") (pinfunction "1_1") (pintype "passive"))
      (node (ref "U1") (pin "1") (pinfunction "~{CS}_1") (pintype "input"))
      (node (ref "U2") (pin "12") (pinfunction "IO11_12") (pintype "bidirectional"))
    )
    (net (code "12") (name "GDR") (class "Default")
      (node (ref "J1") (pin "2") (pinfunction "2_2") (pintype "bidirectional"))
      (node (ref "Q1") (pin "1") (pinfunction "G_1") (pintype "bidirectional"))
      (node (ref "R4") (pin "2") (pinfunction "2_2") (pintype "passive"))
    )
    (net (code "13") (name "GND") (class "Default")
      (node (ref "BOOT_BUTTON") (pin "1") (pinfunction "1_1") (pintype "passive"))
      (node (ref "BOOT_BUTTON") (pin "2") (pinfunction "2_2") (pintype "passive"))
      (node (ref "C1") (pin "2") (pinfunction "2_2") (pintype "passive"))
      (node (ref "C10") (pin "2") (pinfunction "2_2") (pintype "passive"))
      (node (ref "C10_SUPERCAP") (pin "1") (pinfunction "1_1") (pintype "passive"))
      (node (ref "C1_BAT") (pin "2") (pinfunction "2_2") (pintype "passive"))
      (node (ref "C1_BAT1") (pin "2") (pinfunction "2_2") (pintype "passive"))
      (node (ref "C1_BAT2") (pin "2") (pinfunction "2_2") (pintype "passive"))
      (node (ref "C2") (pin "2") (pinfunction "2_2") (pintype "passive"))
      (node (ref "C2_BAT") (pin "2") (pinfunction "2_2") (pintype "passive"))
      (node (ref "C3") (pin "-") (pinfunction "-_-") (pintype "passive"))
      (node (ref "C4_USB") (pin "2") (pinfunction "2_2") (pintype "passive"))
      (node (ref "C5") (pin "2") (pinfunction "2_2") (pintype "passive"))
      (node (ref "C5_USB") (pin "2") (pinfunction "2_2") (pintype "passive"))
      (node (ref "C6") (pin "2") (pinfunction "2_2") (pintype "passive"))
      (node (ref "C7") (pin "2") (pinfunction "2_2") (pintype "passive"))
      (node (ref "C8") (pin "2") (pinfunction "2_2") (pintype "passive"))
      (node (ref "C9") (pin "2") (pinfunction "2_2") (pintype "passive"))
      (node (ref "CHANGE_BUTTON") (pin "1") (pinfunction "1_1") (pintype "passive"))
      (node (ref "CHANGE_BUTTON") (pin "2") (pinfunction "2_2") (pintype "passive"))
      (node (ref "C_DELAY") (pin "2") (pinfunction "2_2") (pintype "passive"))
      (node (ref "D1") (pin "2") (pinfunction "GND_2") (pintype "bidirectional"))
      (node (ref "D10") (pin "1") (pinfunction "1_1") (pintype "passive"))
      (node (ref "D11") (pin "1") (pinfunction "1_1") (pintype "passive"))
      (node (ref "D12") (pin "1") (pinfunction "1_1") (pintype "passive"))
      (node (ref "D3") (pin "1") (pinfunction "K_1") (pintype "bidirectional"))
      (node (ref "D6") (pin "1") (pinfunction "1_1") (pintype "passive"))
      (node (ref "D8") (pin "1") (pinfunction "1_1") (pintype "passive"))
      (node (ref "D9") (pin "1") (pinfunction "1_1") (pintype "passive"))
      (node (ref "EPD_C1") (pin "1") (pinfunction "1_1") (pintype "passive"))
      (node (ref "EPD_C10") (pin "1") (pinfunction "1_1") (pintype "passive"))
      (node (ref "EPD_C11") (pin "1") (pinfunction "1_1") (pintype "passive"))
      (node (ref "EPD_C12") (pin "1") (pinfunction "1_1") (pintype "passive"))
      (node (ref "EPD_C2") (pin "1") (pinfunction "1_1") (pintype "passive"))
      (node (ref "EPD_C5") (pin "1") (pinfunction "1_1") (pintype "passive"))
      (node (ref "EPD_C6") (pin "1") (pinfunction "1_1") (pintype "passive"))
      (node (ref "EPD_C7") (pin "1") (pinfunction "1_1") (pintype "passive"))
      (node (ref "EPD_C8") (pin "1") (pinfunction "1_1") (pintype "passive"))
      (node (ref "EPD_C9") (pin "1") (pinfunction "1_1") (pintype "passive"))
      (node (ref "IC1") (pin "3") (pinfunction "GND_3") (pintype "bidirectional"))
      (node (ref "IC4") (pin "2") (pinfunction "VSS_2") (pintype "bidirectional"))
      (node (ref "J1") (pin "17") (pinfunction "17_17") (pintype "bidirectional"))
      (node (ref "J1") (pin "8") (pinfunction "8_8") (pintype "bidirectional"))
      (node (ref "J1") (pin "MP1") (pinfunction "MP1_MP1") (pintype "bidirectional"))
      (node (ref "J1") (pin "MP2") (pinfunction "MP2_MP2") (pintype "bidirectional"))
      (node (ref "J2") (pin "A1") (pinfunction "A1_A1") (pintype "bidirectional"))
      (node (ref "J2") (pin "A12") (pinfunction "A12_A12") (pintype "bidirectional"))
      (node (ref "J2") (pin "B1") (pinfunction "B1_B1") (pintype "bidirectional"))
      (node (ref "J2") (pin "B12") (pinfunction "B12_B12") (pintype "bidirectional"))
      (node (ref "J2") (pin "MP1") (pinfunction "MP1_MP1") (pintype "bidirectional"))
      (node (ref "J2") (pin "MP2") (pinfunction "MP2_MP2") (pintype "bidirectional"))
      (node (ref "J2") (pin "MP3") (pinfunction "MP3_MP3") (pintype "bidirectional"))
      (node (ref "J2") (pin "MP4") (pinfunction "MP4_MP4") (pintype "bidirectional"))
      (node (ref "J3") (pin "1") (pinfunction "1_1") (pintype "power_in"))
      (node (ref "J4") (pin "G1") (pinfunction "GND_1_G1") (pintype "bidirectional"))
      (node (ref "J4") (pin "G2") (pinfunction "GND_2_G2") (pintype "bidirectional"))
      (node (ref "J4") (pin "G3") (pinfunction "GND_3_G3") (pintype "bidirectional"))
      (node (ref "J4") (pin "G4") (pinfunction "GND_4_G4") (pintype "bidirectional"))
      (node (ref "J4") (pin "P6") (pinfunction "VSS_P6") (pintype "bidirectional"))
      (node (ref "R1_PWRUSB") (pin "1") (pinfunction "1_1") (pintype "passive"))
      (node (ref "R2") (pin "1") (pinfunction "1_1") (pintype "passive"))
      (node (ref "R2-USB") (pin "2") (pinfunction "2_2") (pintype "passive"))
      (node (ref "R2-USB1") (pin "1") (pinfunction "1_1") (pintype "passive"))
      (node (ref "R2_BAT") (pin "1") (pinfunction "1_1") (pintype "passive"))
      (node (ref "R4") (pin "1") (pinfunction "1_1") (pintype "passive"))
      (node (ref "RESET_BUTTON") (pin "1") (pinfunction "1_1") (pintype "passive"))
      (node (ref "RESET_BUTTON") (pin "2") (pinfunction "2_2") (pintype "passive"))
      (node (ref "SENSOR2") (pin "1") (pinfunction "GND_1") (pintype "power_in"))
      (node (ref "SENSOR2") (pin "5") (pinfunction "SDO_5") (pintype "bidirectional"))
      (node (ref "SENSOR2") (pin "7") (pinfunction "GND_7") (pintype "power_in"))
      (node (ref "SJ1") (pin "1") (pinfunction "1_1") (pintype "passive"))
      (node (ref "TP4") (pin "TP") (pinfunction "TP_TP") (pintype "input"))
      (node (ref "TP5") (pin "TP") (pinfunction "TP_TP") (pintype "input"))
      (node (ref "U") (pin "2") (pinfunction "VSS_2") (pintype "power_in"))
      (node (ref "U1") (pin "4") (pinfunction "GND_4") (pintype "power_in"))
      (node (ref "U1") (pin "9") (pinfunction "EXP_9") (pintype "passive"))
      (node (ref "U2") (pin "1") (pinfunction "GND_1") (pintype "power_in"))
      (node (ref "U2") (pin "28") (pinfunction "GND_28") (pintype "power_in"))
      (node (ref "U2") (pin "29_1") (pinfunction "GND_29_1") (pintype "power_in"))
      (node (ref "U2") (pin "29_2") (pinfunction "GND_29_2") (pintype "power_in"))
      (node (ref "U2") (pin "29_3") (pinfunction "GND_29_3") (pintype "power_in"))
      (node (ref "U2") (pin "29_4") (pinfunction "GND_29_4") (pintype "power_in"))
      (node (ref "U2") (pin "29_5") (pinfunction "GND_29_5") (pintype "power_in"))
      (node (ref "U2") (pin "29_6") (pinfunction "GND_29_6") (pintype "power_in"))
      (node (ref "U2") (pin "29_7") (pinfunction "GND_29_7") (pintype "power_in"))
      (node (ref "U2") (pin "29_8") (pinfunction "GND_29_8") (pintype "power_in"))
      (node (ref "U2") (pin "29_9") (pinfunction "GND_29_9") (pintype "power_in"))
      (node (ref "U3") (pin "13") (pinfunction "GND_13") (pintype "power_in"))
      (node (ref "U4") (pin "1") (pinfunction "CTG_1") (pintype "power_in"))
      (node (ref "U4") (pin "4") (pinfunction "GND_4") (pintype "power_in"))
      (node (ref "U4") (pin "6") (pinfunction "QSTRT_6") (pintype "input"))
      (node (ref "U4") (pin "9") (pinfunction "EP_9") (pintype "power_in"))
    )
    (net (code "14") (name "GPIO8") (class "Default")
      (node (ref "R1") (pin "1") (pinfunction "1_1") (pintype "passive"))
      (node (ref "U2") (pin "10") (pinfunction "IO8_10") (pintype "bidirectional"))
    )
    (net (code "15") (name "I2C_PW") (class "Default")
      (node (ref "C1") (pin "1") (pinfunction "1_1") (pintype "passive"))
      (node (ref "C2") (pin "1") (pinfunction "1_1") (pintype "passive"))
      (node (ref "R1-PINH") (pin "2") (pinfunction "2_2") (pintype "passive"))
      (node (ref "R2-PINH") (pin "2") (pinfunction "2_2") (pintype "passive"))
      (node (ref "SENSOR2") (pin "2") (pinfunction "CSB_2") (pintype "input"))
      (node (ref "SENSOR2") (pin "6") (pinfunction "VDDIO_6") (pintype "power_in"))
      (node (ref "SENSOR2") (pin "8") (pinfunction "VDD_8") (pintype "power_in"))
      (node (ref "U2") (pin "17") (pinfunction "IO19_17") (pintype "bidirectional"))
    )
    (net (code "16") (name "INT_RTC") (class "Default")
      (node (ref "R1-PINH1") (pin "1") (pinfunction "1_1") (pintype "passive"))
      (node (ref "TP15") (pin "TP") (pinfunction "TP_TP") (pintype "input"))
      (node (ref "U2") (pin "8") (pinfunction "IO0_8") (pintype "bidirectional"))
      (node (ref "U3") (pin "3") (pinfunction "SQW/~{INT}_3") (pintype "output"))
    )
    (net (code "17") (name "IO{slash}BOOT") (class "Default")
      (node (ref "BOOT_BUTTON") (pin "3") (pinfunction "3_3") (pintype "passive"))
      (node (ref "BOOT_BUTTON") (pin "4") (pinfunction "4_4") (pintype "passive"))
      (node (ref "C6") (pin "1") (pinfunction "1_1") (pintype "passive"))
      (node (ref "R_BOOT") (pin "1") (pinfunction "1_1") (pintype "passive"))
      (node (ref "U2") (pin "15") (pinfunction "IO9_15") (pintype "bidirectional"))
    )
    (net (code "18") (name "IO{slash}CHANGE") (class "Default")
      (node (ref "C10") (pin "1") (pinfunction "1_1") (pintype "passive"))
      (node (ref "CHANGE_BUTTON") (pin "3") (pinfunction "3_3") (pintype "passive"))
      (node (ref "CHANGE_BUTTON") (pin "4") (pinfunction "4_4") (pintype "passive"))
      (node (ref "R_CHANGE") (pin "1") (pinfunction "1_1") (pintype "passive"))
      (node (ref "U2") (pin "23") (pinfunction "IO15_23") (pintype "bidirectional"))
    )
    (net (code "19") (name "MISO") (class "Default")
      (node (ref "D12") (pin "2") (pinfunction "2_2") (pintype "passive"))
      (node (ref "J4") (pin "P7") (pinfunction "DAT0_P7") (pintype "bidirectional"))
      (node (ref "R8") (pin "1") (pinfunction "1_1") (pintype "passive"))
      (node (ref "TP6") (pin "TP") (pinfunction "TP_TP") (pintype "input"))
      (node (ref "U1") (pin "2") (pinfunction "DO(IO1)_2") (pintype "bidirectional"))
      (node (ref "U2") (pin "27") (pinfunction "IO2_27") (pintype "bidirectional"))
    )
    (net (code "20") (name "MOSI") (class "Default")
      (node (ref "D11") (pin "2") (pinfunction "2_2") (pintype "passive"))
      (node (ref "J1") (pin "14") (pinfunction "14_14") (pintype "bidirectional"))
      (node (ref "J4") (pin "P3") (pinfunction "CMD_P3") (pintype "bidirectional"))
      (node (ref "R7") (pin "1") (pinfunction "1_1") (pintype "passive"))
      (node (ref "TP7") (pin "TP") (pinfunction "TP_TP") (pintype "input"))
      (node (ref "U1") (pin "5") (pinfunction "DI(IO0)_5") (pintype "bidirectional"))
      (node (ref "U2") (pin "7") (pinfunction "IO7_7") (pintype "bidirectional"))
    )
    (net (code "21") (name "Net-(D2-CATHODE)") (class "Default")
      (node (ref "C1_BAT1") (pin "1") (pinfunction "1_1") (pintype "passive"))
      (node (ref "D2") (pin "1") (pinfunction "CATHODE_1") (pintype "bidirectional"))
      (node (ref "IC4") (pin "1") (pinfunction "VIN_1") (pintype "bidirectional"))
      (node (ref "IC4") (pin "3") (pinfunction "CE_3") (pintype "bidirectional"))
      (node (ref "Q3") (pin "2") (pinfunction "S_2") (pintype "bidirectional"))
    )
    (net (code "22") (name "Net-(D3-A)") (class "Default")
      (node (ref "C4") (pin "1") (pinfunction "1_1") (pintype "passive"))
      (node (ref "D3") (pin "2") (pinfunction "A_2") (pintype "bidirectional"))
      (node (ref "D4") (pin "1") (pinfunction "K_1") (pintype "bidirectional"))
    )
    (net (code "23") (name "Net-(D7-CATHODE)") (class "Default")
      (node (ref "D7") (pin "1") (pinfunction "CATHODE_1") (pintype "bidirectional"))
      (node (ref "R_CAPACITOR") (pin "1") (pinfunction "1_1") (pintype "passive"))
    )
    (net (code "24") (name "Net-(EPD_C1-Pad2)") (class "Default")
      (node (ref "EPD_C1") (pin "2") (pinfunction "2_2") (pintype "passive"))
      (node (ref "J1") (pin "4") (pinfunction "4_4") (pintype "bidirectional"))
    )
    (net (code "25") (name "Net-(EPD_C2-Pad2)") (class "Default")
      (node (ref "EPD_C2") (pin "2") (pinfunction "2_2") (pintype "passive"))
      (node (ref "J1") (pin "5") (pinfunction "5_5") (pintype "bidirectional"))
    )
    (net (code "26") (name "Net-(EPD_C6-Pad2)") (class "Default")
      (node (ref "EPD_C6") (pin "2") (pinfunction "2_2") (pintype "passive"))
      (node (ref "J1") (pin "18") (pinfunction "18_18") (pintype "bidirectional"))
    )
    (net (code "27") (name "Net-(EPD_C7-Pad2)") (class "Default")
      (node (ref "EPD_C7") (pin "2") (pinfunction "2_2") (pintype "passive"))
      (node (ref "J1") (pin "19") (pinfunction "19_19") (pintype "bidirectional"))
    )
    (net (code "28") (name "Net-(EPD_C8-Pad2)") (class "Default")
      (node (ref "EPD_C8") (pin "2") (pinfunction "2_2") (pintype "passive"))
      (node (ref "J1") (pin "20") (pinfunction "20_20") (pintype "bidirectional"))
    )
    (net (code "29") (name "Net-(EPD_C10-Pad2)") (class "Default")
      (node (ref "EPD_C10") (pin "2") (pinfunction "2_2") (pintype "passive"))
      (node (ref "J1") (pin "22") (pinfunction "22_22") (pintype "bidirectional"))
    )
    (net (code "30") (name "Net-(EPD_C12-Pad2)") (class "Default")
      (node (ref "EPD_C12") (pin "2") (pinfunction "2_2") (pintype "passive"))
      (node (ref "J1") (pin "24") (pinfunction "24_24") (pintype "bidirectional"))
    )
    (net (code "31") (name "Net-(GHC_LED-PadC)") (class "Default")
      (node (ref "GHC_LED") (pin "C") (pinfunction "C_C") (pintype "passive"))
      (node (ref "R1_BAT") (pin "1") (pinfunction "1_1") (pintype "passive"))
    )
    (net (code "32") (name "Net-(IC1-CT)") (class "Default")
      (node (ref "C_DELAY") (pin "1") (pinfunction "1_1") (pintype "passive"))
      (node (ref "IC1") (pin "5") (pinfunction "CT_5") (pintype "bidirectional"))
    )
    (net (code "33") (name "Net-(J2-PadA5)") (class "Default")
      (node (ref "J2") (pin "A5") (pinfunction "A5_A5") (pintype "bidirectional"))
      (node (ref "R2-USB1") (pin "2") (pinfunction "2_2") (pintype "passive"))
    )
    (net (code "34") (name "Net-(J2-PadB5)") (class "Default")
      (node (ref "J2") (pin "B5") (pinfunction "B5_B5") (pintype "bidirectional"))
      (node (ref "R2-USB") (pin "1") (pinfunction "1_1") (pintype "passive"))
    )
    (net (code "35") (name "Net-(U-PROG)") (class "Default")
      (node (ref "R2_BAT") (pin "2") (pinfunction "2_2") (pintype "passive"))
      (node (ref "U") (pin "5") (pinfunction "PROG_5") (pintype "input"))
    )
    (net (code "36") (name "Net-(U-STAT)") (class "Default")
      (node (ref "R1_BAT") (pin "2") (pinfunction "2_2") (pintype "passive"))
      (node (ref "U") (pin "1") (pinfunction "STAT_1") (pintype "output"))
    )
    (net (code "37") (name "PREVGH") (class "Default")
      (node (ref "D5") (pin "1") (pinfunction "K_1") (pintype "bidirectional"))
      (node (ref "EPD_C9") (pin "2") (pinfunction "2_2") (pintype "passive"))
      (node (ref "J1") (pin "21") (pinfunction "21_21") (pintype "bidirectional"))
    )
    (net (code "38") (name "PREVGL") (class "Default")
      (node (ref "D4") (pin "2") (pinfunction "A_2") (pintype "bidirectional"))
      (node (ref "EPD_C11") (pin "2") (pinfunction "2_2") (pintype "passive"))
      (node (ref "J1") (pin "23") (pinfunction "23_23") (pintype "bidirectional"))
    )
    (net (code "39") (name "RESE") (class "Default")
      (node (ref "J1") (pin "3") (pinfunction "3_3") (pintype "bidirectional"))
      (node (ref "Q1") (pin "2") (pinfunction "S_2") (pintype "bidirectional"))
      (node (ref "R3") (pin "2") (pinfunction "2_2") (pintype "passive"))
      (node (ref "SJ1") (pin "2") (pinfunction "2_2") (pintype "passive"))
    )
    (net (code "40") (name "RESE'") (class "Default")
      (node (ref "R2") (pin "2") (pinfunction "2_2") (pintype "passive"))
      (node (ref "R3") (pin "1") (pinfunction "1_1") (pintype "passive"))
    )
    (net (code "41") (name "RESET") (class "Default")
      (node (ref "C5") (pin "1") (pinfunction "1_1") (pintype "passive"))
      (node (ref "IC1") (pin "1") (pinfunction "VOUT_1") (pintype "bidirectional"))
      (node (ref "RESET_BUTTON") (pin "3") (pinfunction "3_3") (pintype "passive"))
      (node (ref "RESET_BUTTON") (pin "4") (pinfunction "4_4") (pintype "passive"))
      (node (ref "R_RESET") (pin "1") (pinfunction "1_1") (pintype "passive"))
      (node (ref "U2") (pin "3") (pinfunction "EN_3") (pintype "input"))
    )
    (net (code "42") (name "RTC_RST") (class "Default")
      (node (ref "U2") (pin "16") (pinfunction "IO18_16") (pintype "bidirectional"))
      (node (ref "U3") (pin "4") (pinfunction "~{RST}_4") (pintype "input"))
    )
    (net (code "43") (name "RX") (class "Default")
      (node (ref "TP2") (pin "TP") (pinfunction "TP_TP") (pintype "input"))
      (node (ref "U2") (pin "24") (pinfunction "RXD0/GPIO17_24") (pintype "bidirectional"))
    )
    (net (code "44") (name "SCK") (class "Default")
      (node (ref "D10") (pin "2") (pinfunction "2_2") (pintype "passive"))
      (node (ref "J1") (pin "13") (pinfunction "13_13") (pintype "bidirectional"))
      (node (ref "J4") (pin "P5") (pinfunction "CLK_P5") (pintype "bidirectional"))
      (node (ref "R6") (pin "1") (pinfunction "1_1") (pintype "passive"))
      (node (ref "TP8") (pin "TP") (pinfunction "TP_TP") (pintype "input"))
      (node (ref "U1") (pin "6") (pinfunction "CLK_6") (pintype "input"))
      (node (ref "U2") (pin "6") (pinfunction "IO6_6") (pintype "bidirectional"))
    )
    (net (code "45") (name "SCL") (class "Default")
      (node (ref "J3") (pin "4") (pinfunction "4_4") (pintype "passive"))
      (node (ref "R2-PINH") (pin "1") (pinfunction "1_1") (pintype "passive"))
      (node (ref "SENSOR2") (pin "4") (pinfunction "SCK_4") (pintype "input"))
      (node (ref "U2") (pin "20") (pinfunction "IO22_20") (pintype "bidirectional"))
      (node (ref "U3") (pin "16") (pinfunction "SCL_16") (pintype "input"))
      (node (ref "U4") (pin "7") (pinfunction "SCL_7") (pintype "input"))
    )
    (net (code "46") (name "SDA") (class "Default")
      (node (ref "J3") (pin "3") (pinfunction "3_3") (pintype "passive"))
      (node (ref "R1-PINH") (pin "1") (pinfunction "1_1") (pintype "passive"))
      (node (ref "SENSOR2") (pin "3") (pinfunction "SDI_3") (pintype "bidirectional"))
      (node (ref "U2") (pin "19") (pinfunction "IO21_19") (pintype "bidirectional"))
      (node (ref "U3") (pin "15") (pinfunction "SDA_15") (pintype "bidirectional"))
      (node (ref "U4") (pin "8") (pinfunction "SDA_8") (pintype "bidirectional"))
    )
    (net (code "47") (name "SRC") (class "Default")
      (node (ref "C4") (pin "2") (pinfunction "2_2") (pintype "passive"))
      (node (ref "D5") (pin "2") (pinfunction "A_2") (pintype "bidirectional"))
      (node (ref "L1") (pin "1") (pinfunction "1_1") (pintype "passive"))
      (node (ref "Q1") (pin "3") (pinfunction "D_3") (pintype "bidirectional"))
    )
    (net (code "48") (name "SS_SD") (class "Default")
      (node (ref "D8") (pin "2") (pinfunction "2_2") (pintype "passive"))
      (node (ref "J4") (pin "P2") (pinfunction "CD/DAT3_P2") (pintype "bidirectional"))
      (node (ref "R10") (pin "1") (pinfunction "1_1") (pintype "passive"))
      (node (ref "U2") (pin "4") (pinfunction "IO4_4") (pintype "bidirectional"))
    )
    (net (code "49") (name "TX") (class "Default")
      (node (ref "TP1") (pin "TP") (pinfunction "TP_TP") (pintype "input"))
      (node (ref "U2") (pin "25") (pinfunction "TXD0/GPIO16_25") (pintype "bidirectional"))
    )
    (net (code "50") (name "USB_D+") (class "Default")
      (node (ref "D1") (pin "1") (pinfunction "I/O1_1_1") (pintype "bidirectional"))
      (node (ref "U2") (pin "14") (pinfunction "IO13_14") (pintype "bidirectional"))
    )
    (net (code "51") (name "USB_D-") (class "Default")
      (node (ref "D1") (pin "3") (pinfunction "I/O2_1_3") (pintype "bidirectional"))
      (node (ref "U2") (pin "13") (pinfunction "IO12_13") (pintype "bidirectional"))
    )
    (net (code "52") (name "VBAT") (class "Default")
      (node (ref "C2_BAT") (pin "1") (pinfunction "1_1") (pintype "passive"))
      (node (ref "Q3") (pin "3") (pinfunction "D_3") (pintype "bidirectional"))
      (node (ref "TP3") (pin "TP") (pinfunction "TP_TP") (pintype "input"))
      (node (ref "U") (pin "3") (pinfunction "VBAT_3") (pintype "power_in"))
      (node (ref "U4") (pin "2") (pinfunction "CELL_2") (pintype "power_in"))
      (node (ref "U4") (pin "3") (pinfunction "VDD_3") (pintype "power_in"))
    )
    (net (code "53") (name "VBUS") (class "Default")
      (node (ref "C1_BAT") (pin "1") (pinfunction "1_1") (pintype "passive"))
      (node (ref "C4_USB") (pin "1") (pinfunction "1_1") (pintype "passive"))
      (node (ref "C5_USB") (pin "1") (pinfunction "1_1") (pintype "passive"))
      (node (ref "D1") (pin "5") (pinfunction "VBUS_5") (pintype "bidirectional"))
      (node (ref "D2") (pin "2") (pinfunction "ANODE_2") (pintype "bidirectional"))
      (node (ref "GHC_LED") (pin "A") (pinfunction "A_A") (pintype "passive"))
      (node (ref "PFMF.050.1") (pin "2") (pinfunction "2_2") (pintype "passive"))
      (node (ref "Q3") (pin "1") (pinfunction "G_1") (pintype "bidirectional"))
      (node (ref "R1_PWRUSB") (pin "2") (pinfunction "2_2") (pintype "passive"))
      (node (ref "TP14") (pin "TP") (pinfunction "TP_TP") (pintype "input"))
      (node (ref "U") (pin "4") (pinfunction "VIN_4") (pintype "power_in"))
    )
    (net (code "54") (name "VRTC") (class "Default")
      (node (ref "C10_SUPERCAP") (pin "2") (pinfunction "2_2") (pintype "passive"))
      (node (ref "C8") (pin "1") (pinfunction "1_1") (pintype "passive"))
      (node (ref "R_CAPACITOR") (pin "2") (pinfunction "2_2") (pintype "passive"))
      (node (ref "U3") (pin "14") (pinfunction "VBAT_14") (pintype "power_in"))
    )
    (net (code "55") (name "VUSB") (class "Default")
      (node (ref "J2") (pin "A4") (pinfunction "A4_A4") (pintype "bidirectional"))
      (node (ref "J2") (pin "A9") (pinfunction "A9_A9") (pintype "bidirectional"))
      (node (ref "J2") (pin "B4") (pinfunction "B4_B4") (pintype "bidirectional"))
      (node (ref "J2") (pin "B9") (pinfunction "B9_B9") (pintype "bidirectional"))
      (node (ref "PFMF.050.1") (pin "1") (pinfunction "1_1") (pintype "passive"))
    )
    (net (code "56") (name "unconnected-(IC1-NC-Pad4)") (class "Default")
      (node (ref "IC1") (pin "4") (pinfunction "NC_4") (pintype "no_connect"))
    )
    (net (code "57") (name "unconnected-(IC4-NC-Pad4)") (class "Default")
      (node (ref "IC4") (pin "4") (pinfunction "NC_4") (pintype "no_connect"))
    )
    (net (code "58") (name "unconnected-(J1-Pad1)") (class "Default")
      (node (ref "J1") (pin "1") (pinfunction "1_1") (pintype "bidirectional"))
    )
    (net (code "59") (name "unconnected-(J1-Pad6)") (class "Default")
      (node (ref "J1") (pin "6") (pinfunction "6_6") (pintype "bidirectional"))
    )
    (net (code "60") (name "unconnected-(J1-Pad7)") (class "Default")
      (node (ref "J1") (pin "7") (pinfunction "7_7") (pintype "bidirectional"))
    )
    (net (code "61") (name "unconnected-(J2-PadA8)") (class "Default")
      (node (ref "J2") (pin "A8") (pinfunction "A8_A8") (pintype "bidirectional"))
    )
    (net (code "62") (name "unconnected-(J2-PadB8)") (class "Default")
      (node (ref "J2") (pin "B8") (pinfunction "B8_B8") (pintype "bidirectional"))
    )
    (net (code "63") (name "unconnected-(J4-DAT1-PadP8)") (class "Default")
      (node (ref "J4") (pin "P8") (pinfunction "DAT1_P8") (pintype "bidirectional"))
    )
    (net (code "64") (name "unconnected-(J4-DAT2-PadP1)") (class "Default")
      (node (ref "J4") (pin "P1") (pinfunction "DAT2_P1") (pintype "bidirectional"))
    )
    (net (code "65") (name "unconnected-(J4-DETECTION_1-PadS1)") (class "Default")
      (node (ref "J4") (pin "S1") (pinfunction "DETECTION_1_S1") (pintype "bidirectional"))
    )
    (net (code "66") (name "unconnected-(J4-DETECTION_2-PadS2)") (class "Default")
      (node (ref "J4") (pin "S2") (pinfunction "DETECTION_2_S2") (pintype "bidirectional"))
    )
    (net (code "67") (name "unconnected-(U2-NC-Pad22)") (class "Default")
      (node (ref "U2") (pin "22") (pinfunction "NC_22") (pintype "no_connect"))
    )
    (net (code "68") (name "unconnected-(U4-~{ALERT}-Pad5)") (class "Default")
      (node (ref "U4") (pin "5") (pinfunction "~{ALERT}_5") (pintype "output"))
    )
  )
)
